# WL_BPF.net
KiCad netlist of a schematic drawn in Altium Designer
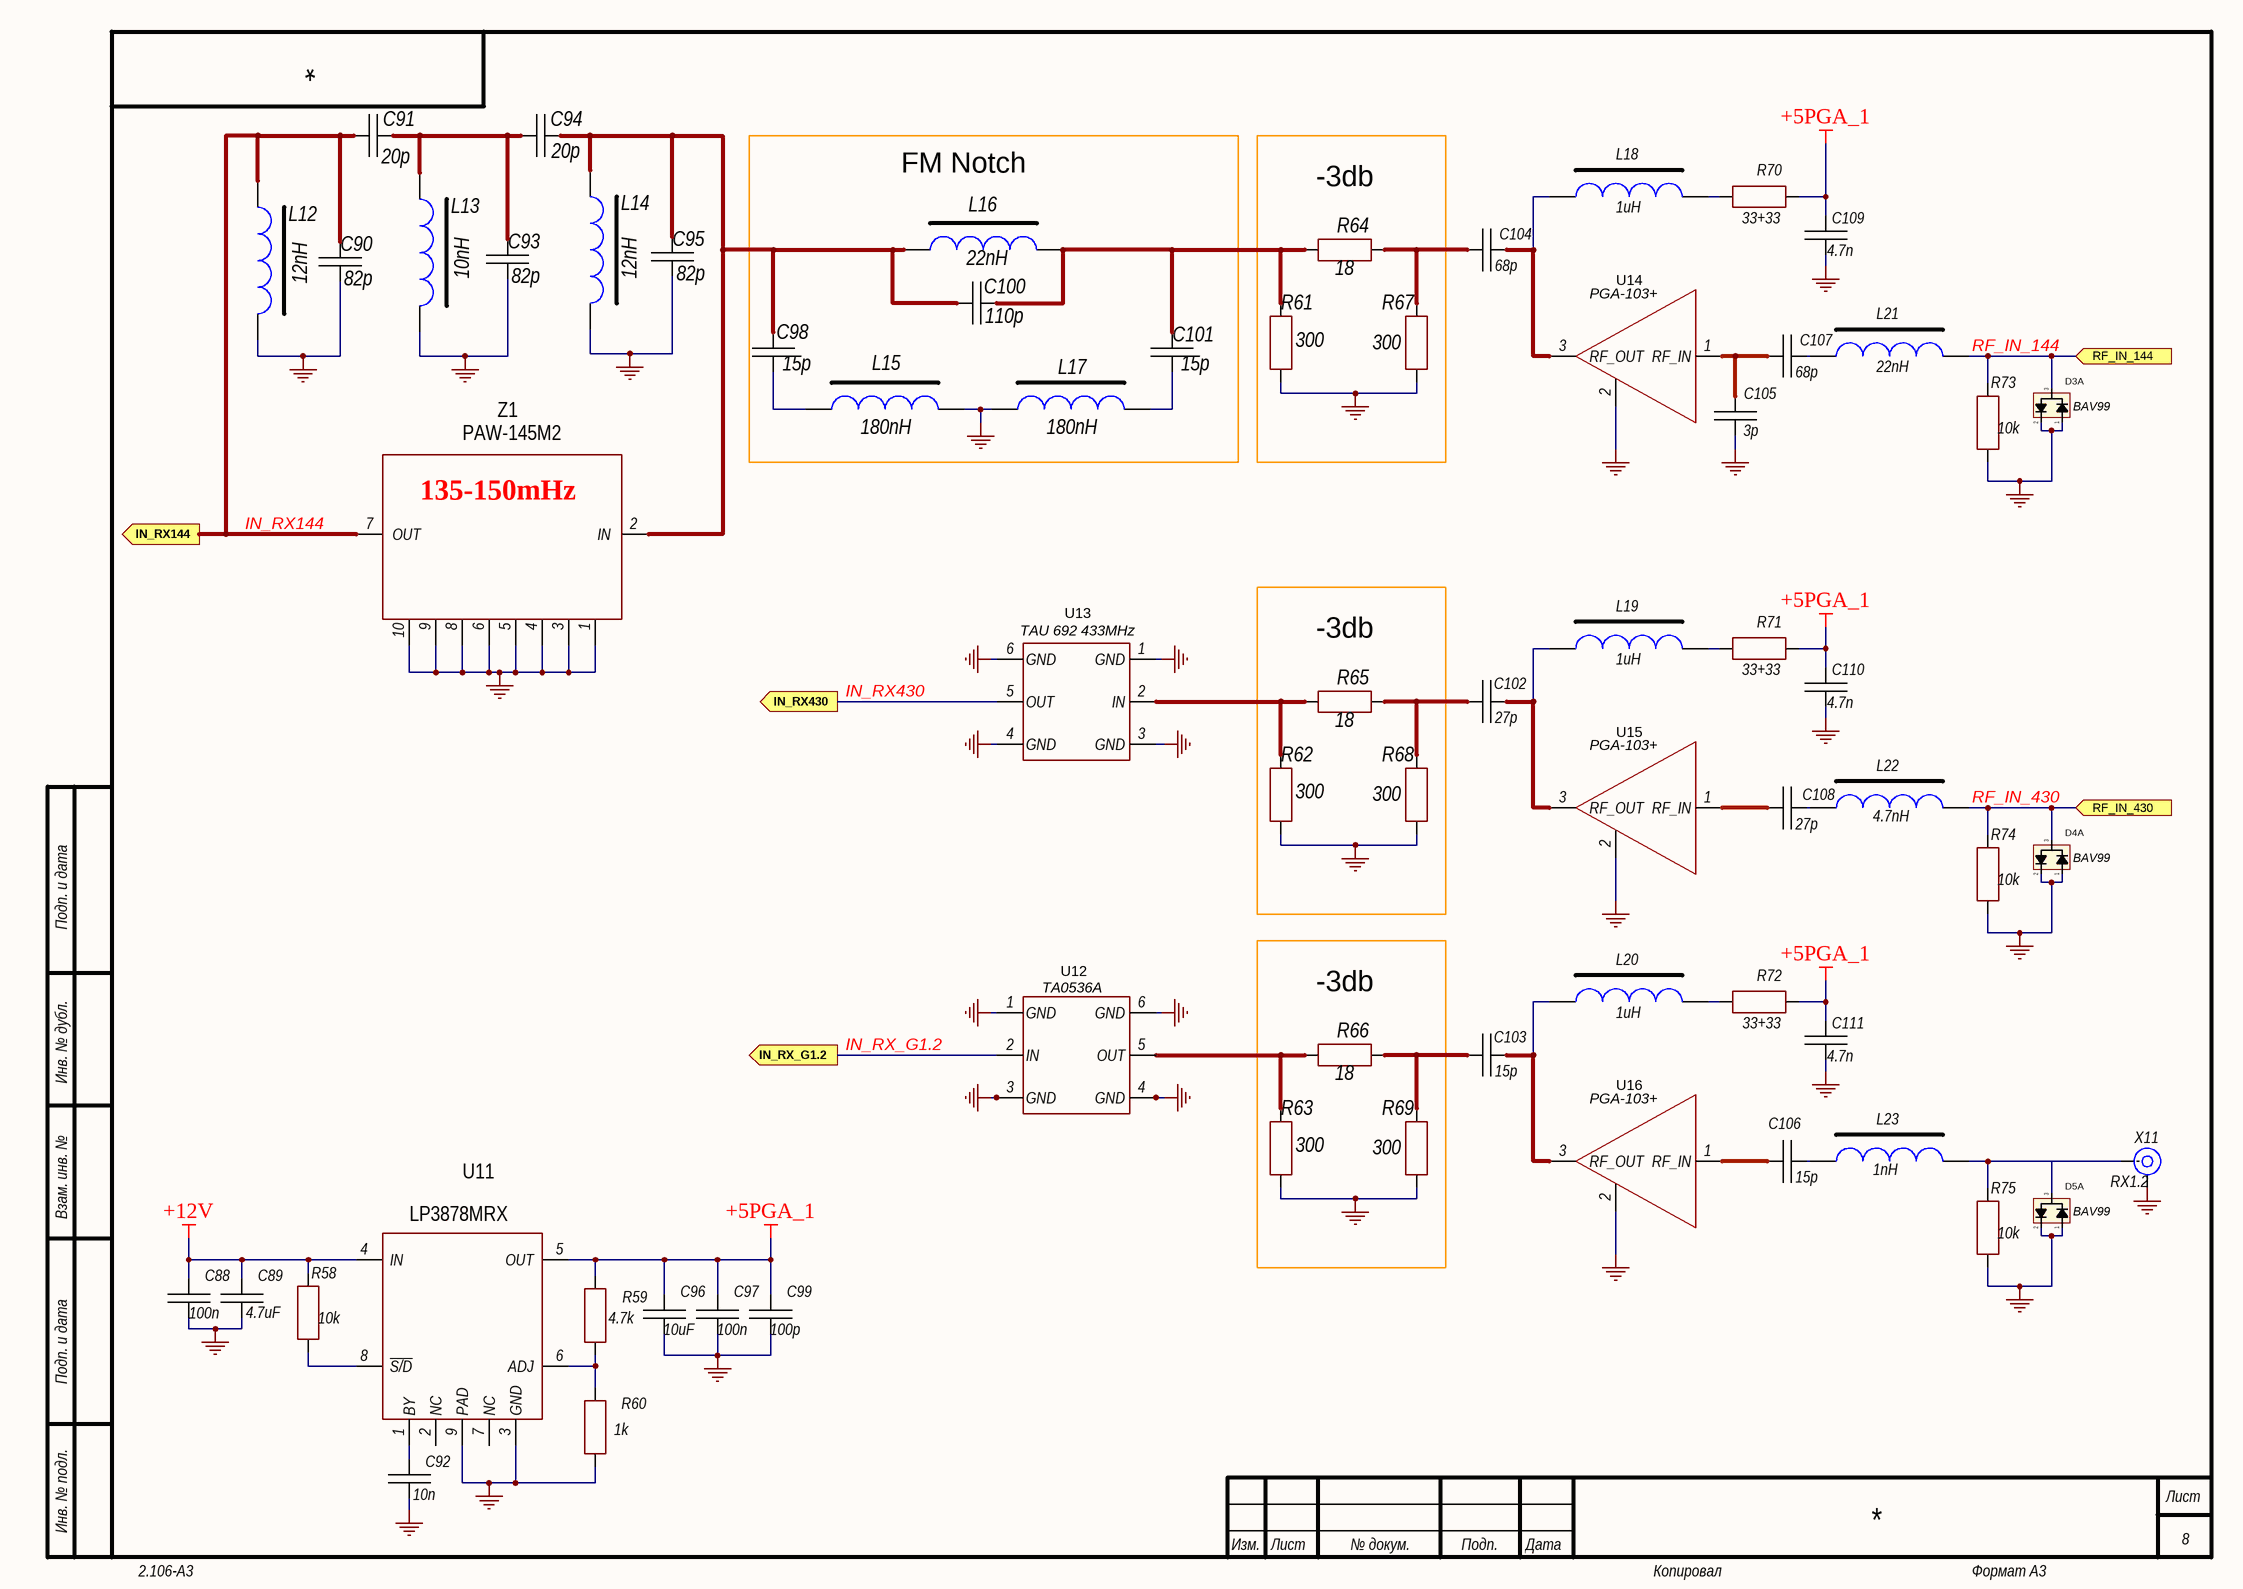
[diagram p0: WL_BPF.SchDoc]

(export (version "E")
  (design (tool "Eeschema 10.0.6"))
  (components
    (comp (ref "C88")
      (value "100n")
      (footprint "standard:CH0805C")
      (libsource (lib "Discrete") (part "Capacitor"))
    )
    (comp (ref "C89")
      (value "4.7uF")
      (footprint "standard:CH0805C")
      (libsource (lib "Discrete") (part "Capacitor"))
    )
    (comp (ref "C90")
      (value "82p")
      (footprint "standard:CH0805C")
      (libsource (lib "Discrete") (part "Capacitor"))
    )
    (comp (ref "C91")
      (value "20p")
      (footprint "standard:CH0805C")
      (libsource (lib "Discrete") (part "Capacitor"))
    )
    (comp (ref "C92")
      (value "10n")
      (footprint "standard:CH0805C")
      (libsource (lib "Discrete") (part "Capacitor"))
    )
    (comp (ref "C93")
      (value "82p")
      (footprint "standard:CH0805C")
      (libsource (lib "Discrete") (part "Capacitor"))
    )
    (comp (ref "C94")
      (value "20p")
      (footprint "standard:CH0805C")
      (libsource (lib "Discrete") (part "Capacitor"))
    )
    (comp (ref "C95")
      (value "82p")
      (footprint "standard:CH0805C")
      (libsource (lib "Discrete") (part "Capacitor"))
    )
    (comp (ref "C96")
      (value "10uF")
      (footprint "standard:CH0805C")
      (libsource (lib "Discrete") (part "Capacitor"))
    )
    (comp (ref "C97")
      (value "100n")
      (footprint "standard:CH0805C")
      (libsource (lib "Discrete") (part "Capacitor"))
    )
    (comp (ref "C98")
      (value "15p")
      (footprint "standard:CH0805C")
      (libsource (lib "Discrete") (part "Capacitor"))
    )
    (comp (ref "C99")
      (value "100p")
      (footprint "standard:CH0805C")
      (libsource (lib "Discrete") (part "Capacitor"))
    )
    (comp (ref "C100")
      (value "110p")
      (footprint "standard:CH0805C")
      (libsource (lib "Discrete") (part "Capacitor"))
    )
    (comp (ref "C101")
      (value "15p")
      (footprint "standard:CH0805C")
      (libsource (lib "Discrete") (part "Capacitor"))
    )
    (comp (ref "C102")
      (value "27p")
      (footprint "standard:CH0805C")
      (libsource (lib "Discrete") (part "Capacitor"))
    )
    (comp (ref "C103")
      (value "15p")
      (footprint "standard:CH0603C")
      (libsource (lib "Discrete") (part "Capacitor"))
    )
    (comp (ref "C104")
      (value "68p")
      (footprint "standard:CH0805C")
      (libsource (lib "Discrete") (part "Capacitor"))
    )
    (comp (ref "C105")
      (value "3p")
      (footprint "standard:CH0805C")
      (libsource (lib "Discrete") (part "Capacitor"))
    )
    (comp (ref "C106")
      (value "15p")
      (footprint "standard:CH0603C")
      (libsource (lib "Discrete") (part "Capacitor"))
    )
    (comp (ref "C107")
      (value "68p")
      (footprint "standard:CH0805C")
      (libsource (lib "Discrete") (part "Capacitor"))
    )
    (comp (ref "C108")
      (value "27p")
      (footprint "standard:CH0805C")
      (libsource (lib "Discrete") (part "Capacitor"))
    )
    (comp (ref "C109")
      (value "4.7n")
      (footprint "standard:CH0805C")
      (libsource (lib "Discrete") (part "Capacitor"))
    )
    (comp (ref "C110")
      (value "4.7n")
      (footprint "standard:CH0805C")
      (libsource (lib "Discrete") (part "Capacitor"))
    )
    (comp (ref "C111")
      (value "4.7n")
      (footprint "standard:CH0805C")
      (libsource (lib "Discrete") (part "Capacitor"))
    )
    (comp (ref "D3") (value "BAV99") (footprint "SOT23_132") (libsource (lib "Analog") (part "BAV99")))
    (comp (ref "D4") (value "BAV99") (footprint "SOT23_132") (libsource (lib "Analog") (part "BAV99")))
    (comp (ref "D5") (value "BAV99") (footprint "SOT23_132") (libsource (lib "Analog") (part "BAV99")))
    (comp (ref "L12") (value "12nH") (footprint "L1210") (libsource (lib "") (part "TRANS_1")))
    (comp (ref "L13") (value "10nH") (footprint "L1210") (libsource (lib "") (part "TRANS_1")))
    (comp (ref "L14") (value "12nH") (footprint "L1210") (libsource (lib "") (part "TRANS_1")))
    (comp (ref "L15") (value "180nH") (footprint "L1210") (libsource (lib "") (part "TRANS_1")))
    (comp (ref "L16") (value "22nH") (footprint "L1210") (libsource (lib "") (part "TRANS_1")))
    (comp (ref "L17") (value "180nH") (footprint "L1210") (libsource (lib "") (part "TRANS_1")))
    (comp (ref "L18") (value "1uH") (footprint "L1210") (libsource (lib "Transformers") (part "TRANS")))
    (comp (ref "L19") (value "1uH") (footprint "L1210") (libsource (lib "Transformers") (part "TRANS")))
    (comp (ref "L20") (value "1uH") (footprint "L1210") (libsource (lib "Transformers") (part "TRANS")))
    (comp (ref "L21") (value "22nH") (footprint "L1210") (libsource (lib "Transformers") (part "TRANS")))
    (comp (ref "L22") (value "4.7nH") (footprint "L1210") (libsource (lib "Transformers") (part "TRANS")))
    (comp (ref "L23") (value "1nH") (footprint "L1210") (libsource (lib "Transformers") (part "TRANS")))
    (comp (ref "R58")
      (value "10k")
      (footprint "standard:CH0805R")
      (libsource (lib "Discrete") (part "Resistor"))
    )
    (comp (ref "R59")
      (value "4.7k")
      (footprint "standard:CH0805R")
      (libsource (lib "Discrete") (part "Resistor"))
    )
    (comp (ref "R60")
      (value "1k")
      (footprint "standard:CH0805R")
      (libsource (lib "Discrete") (part "Resistor"))
    )
    (comp (ref "R61") (value "300") (footprint "standard:CH0805R") (libsource (lib "") (part "Resistor_1")))
    (comp (ref "R62") (value "300") (footprint "standard:CH0805R") (libsource (lib "") (part "Resistor_1")))
    (comp (ref "R63") (value "300") (footprint "standard:CH0603R") (libsource (lib "") (part "Resistor_1")))
    (comp (ref "R64") (value "18") (footprint "standard:CH0805R") (libsource (lib "") (part "Resistor_2")))
    (comp (ref "R65") (value "18") (footprint "standard:CH0805R") (libsource (lib "") (part "Resistor_2")))
    (comp (ref "R66") (value "18") (footprint "standard:CH0603R") (libsource (lib "") (part "Resistor_2")))
    (comp (ref "R67") (value "300") (footprint "standard:CH0805R") (libsource (lib "") (part "Resistor_1")))
    (comp (ref "R68") (value "300") (footprint "standard:CH0805R") (libsource (lib "") (part "Resistor_1")))
    (comp (ref "R69") (value "300") (footprint "standard:CH0603R") (libsource (lib "") (part "Resistor_1")))
    (comp (ref "R70") (value "33+33") (footprint "WL_RFFC:CH1206R") (libsource (lib "") (part "Resistor_3")))
    (comp (ref "R71") (value "33+33") (footprint "WL_RFFC:CH1206R") (libsource (lib "") (part "Resistor_3")))
    (comp (ref "R72") (value "33+33") (footprint "WL_RFFC:CH1206R") (libsource (lib "") (part "Resistor_3")))
    (comp (ref "R73")
      (value "10k")
      (footprint "standard:CH0805R")
      (libsource (lib "Discrete") (part "Resistor"))
    )
    (comp (ref "R74")
      (value "10k")
      (footprint "standard:CH0805R")
      (libsource (lib "Discrete") (part "Resistor"))
    )
    (comp (ref "R75") (value "10k") (footprint "standard:CH0805R") (libsource (lib "") (part "Resistor_4")))
    (comp (ref "U11")
      (value "LP3878MRX")
      (footprint "8-SOIC (PAD)")
      (libsource (lib "Power Supplies") (part "LP3878"))
    )
    (comp (ref "U12") (value "TA0536A") (footprint "MA08803") (libsource (lib "") (part "TAU692_1")))
    (comp (ref "U13")
      (value "TAU 692 433MHz")
      (footprint "TAU692")
      (libsource (lib "Digital") (part "TAU692"))
    )
    (comp (ref "U14")
      (value "PGA-103+")
      (footprint "SOT89_123")
      (libsource (lib "Digital") (part "PGA-103+"))
    )
    (comp (ref "U15")
      (value "PGA-103+")
      (footprint "SOT89_123")
      (libsource (lib "Digital") (part "PGA-103+"))
    )
    (comp (ref "U16")
      (value "PGA-103+")
      (footprint "SOT89_123")
      (libsource (lib "Digital") (part "PGA-103+"))
    )
    (comp (ref "X11")
      (value "RX1.2")
      (footprint "CON: u.Fl")
      (description "RF")
      (libsource (lib "Connectors") (part "SMA"))
    )
    (comp (ref "Z1") (value "PAW-145M2") (footprint "PAV") (libsource (lib "Module") (part "SXBP_PAW")))
  )
  (nets
    (net (code "1") (name "+5PGA_1") (class "Default")
      (node (ref "C109") (pin "2") (pinfunction "2_2") (pintype "passive"))
      (node (ref "C110") (pin "2") (pinfunction "2_2") (pintype "passive"))
      (node (ref "C111") (pin "2") (pinfunction "2_2") (pintype "passive"))
      (node (ref "C96") (pin "2") (pinfunction "2_2") (pintype "passive"))
      (node (ref "C97") (pin "2") (pinfunction "2_2") (pintype "passive"))
      (node (ref "C99") (pin "2") (pinfunction "2_2") (pintype "passive"))
      (node (ref "R59") (pin "2") (pinfunction "2_2") (pintype "passive"))
      (node (ref "R70") (pin "2") (pinfunction "2_2") (pintype "passive"))
      (node (ref "R71") (pin "2") (pinfunction "2_2") (pintype "passive"))
      (node (ref "R72") (pin "2") (pinfunction "2_2") (pintype "passive"))
      (node (ref "U11") (pin "5") (pinfunction "OUT_5") (pintype "power_in"))
    )
    (net (code "2") (name "+12V") (class "Default")
      (node (ref "C88") (pin "2") (pinfunction "2_2") (pintype "passive"))
      (node (ref "C89") (pin "2") (pinfunction "2_2") (pintype "passive"))
      (node (ref "R58") (pin "2") (pinfunction "2_2") (pintype "passive"))
      (node (ref "U11") (pin "4") (pinfunction "IN_4") (pintype "power_in"))
    )
    (net (code "3") (name "/IN_RX144") (class "Default")
      (node (ref "C90") (pin "2") (pinfunction "2_2") (pintype "passive"))
      (node (ref "C91") (pin "2") (pinfunction "2_2") (pintype "passive"))
      (node (ref "L12") (pin "1") (pinfunction "1_1") (pintype "passive"))
      (node (ref "Z1") (pin "7") (pinfunction "OUT_7") (pintype "passive"))
    )
    (net (code "4") (name "/IN_RX430") (class "Default")
      (node (ref "U13") (pin "5") (pinfunction "OUT_5") (pintype "passive"))
    )
    (net (code "5") (name "/IN_RX_G1.2") (class "Default")
      (node (ref "U12") (pin "2") (pinfunction "IN_2") (pintype "passive"))
    )
    (net (code "6") (name "/RF_IN_144") (class "Default")
      (node (ref "D3") (pin "3") (pinfunction "9_3") (pintype "passive"))
      (node (ref "L21") (pin "1") (pinfunction "1_1") (pintype "power_in"))
      (node (ref "R73") (pin "2") (pinfunction "2_2") (pintype "passive"))
    )
    (net (code "7") (name "/RF_IN_430") (class "Default")
      (node (ref "D4") (pin "3") (pinfunction "9_3") (pintype "passive"))
      (node (ref "L22") (pin "1") (pinfunction "1_1") (pintype "power_in"))
      (node (ref "R74") (pin "2") (pinfunction "2_2") (pintype "passive"))
    )
    (net (code "8") (name "GND") (class "Default")
      (node (ref "C105") (pin "1") (pinfunction "1_1") (pintype "passive"))
      (node (ref "C109") (pin "1") (pinfunction "1_1") (pintype "passive"))
      (node (ref "C110") (pin "1") (pinfunction "1_1") (pintype "passive"))
      (node (ref "C111") (pin "1") (pinfunction "1_1") (pintype "passive"))
      (node (ref "C88") (pin "1") (pinfunction "1_1") (pintype "passive"))
      (node (ref "C89") (pin "1") (pinfunction "1_1") (pintype "passive"))
      (node (ref "C90") (pin "1") (pinfunction "1_1") (pintype "passive"))
      (node (ref "C92") (pin "1") (pinfunction "1_1") (pintype "passive"))
      (node (ref "C93") (pin "1") (pinfunction "1_1") (pintype "passive"))
      (node (ref "C95") (pin "1") (pinfunction "1_1") (pintype "passive"))
      (node (ref "C96") (pin "1") (pinfunction "1_1") (pintype "passive"))
      (node (ref "C97") (pin "1") (pinfunction "1_1") (pintype "passive"))
      (node (ref "C99") (pin "1") (pinfunction "1_1") (pintype "passive"))
      (node (ref "D3") (pin "1") (pinfunction "11_1") (pintype "passive"))
      (node (ref "D3") (pin "2") (pinfunction "10_2") (pintype "passive"))
      (node (ref "D4") (pin "1") (pinfunction "11_1") (pintype "passive"))
      (node (ref "D4") (pin "2") (pinfunction "10_2") (pintype "passive"))
      (node (ref "D5") (pin "1") (pinfunction "11_1") (pintype "passive"))
      (node (ref "D5") (pin "2") (pinfunction "10_2") (pintype "passive"))
      (node (ref "L12") (pin "2") (pinfunction "2_2") (pintype "passive"))
      (node (ref "L13") (pin "2") (pinfunction "2_2") (pintype "passive"))
      (node (ref "L14") (pin "2") (pinfunction "2_2") (pintype "passive"))
      (node (ref "L15") (pin "2") (pinfunction "2_2") (pintype "passive"))
      (node (ref "L17") (pin "1") (pinfunction "1_1") (pintype "passive"))
      (node (ref "R60") (pin "1") (pinfunction "1_1") (pintype "passive"))
      (node (ref "R61") (pin "2") (pinfunction "2_2") (pintype "passive"))
      (node (ref "R62") (pin "2") (pinfunction "2_2") (pintype "passive"))
      (node (ref "R63") (pin "2") (pinfunction "2_2") (pintype "passive"))
      (node (ref "R67") (pin "2") (pinfunction "2_2") (pintype "passive"))
      (node (ref "R68") (pin "2") (pinfunction "2_2") (pintype "passive"))
      (node (ref "R69") (pin "2") (pinfunction "2_2") (pintype "passive"))
      (node (ref "R73") (pin "1") (pinfunction "1_1") (pintype "passive"))
      (node (ref "R74") (pin "1") (pinfunction "1_1") (pintype "passive"))
      (node (ref "R75") (pin "1") (pinfunction "1_1") (pintype "passive"))
      (node (ref "U11") (pin "3") (pinfunction "GND_3") (pintype "passive"))
      (node (ref "U11") (pin "9") (pinfunction "PAD_9") (pintype "passive"))
      (node (ref "U12") (pin "1") (pinfunction "GND_1") (pintype "passive"))
      (node (ref "U12") (pin "3") (pinfunction "GND_3") (pintype "passive"))
      (node (ref "U12") (pin "4") (pinfunction "GND_4") (pintype "passive"))
      (node (ref "U12") (pin "6") (pinfunction "GND_6") (pintype "passive"))
      (node (ref "U13") (pin "1") (pinfunction "GND_1") (pintype "passive"))
      (node (ref "U13") (pin "3") (pinfunction "GND_3") (pintype "passive"))
      (node (ref "U13") (pin "4") (pinfunction "GND_4") (pintype "passive"))
      (node (ref "U13") (pin "6") (pinfunction "GND_6") (pintype "passive"))
      (node (ref "U14") (pin "2") (pinfunction "GND_2") (pintype "passive"))
      (node (ref "U15") (pin "2") (pinfunction "GND_2") (pintype "passive"))
      (node (ref "U16") (pin "2") (pinfunction "GND_2") (pintype "passive"))
      (node (ref "X11") (pin "2") (pinfunction "IN_2") (pintype "passive"))
      (node (ref "Z1") (pin "1") (pinfunction "RESET_1") (pintype "passive"))
      (node (ref "Z1") (pin "10") (pinfunction "TXD_10") (pintype "passive"))
      (node (ref "Z1") (pin "3") (pinfunction "CH_PD_3") (pintype "passive"))
      (node (ref "Z1") (pin "4") (pinfunction "GPIO16_4") (pintype "passive"))
      (node (ref "Z1") (pin "5") (pinfunction "GPIO14_5") (pintype "passive"))
      (node (ref "Z1") (pin "6") (pinfunction "GPIO0_6") (pintype "passive"))
      (node (ref "Z1") (pin "8") (pinfunction "GPIO5_8") (pintype "passive"))
      (node (ref "Z1") (pin "9") (pinfunction "RXD_9") (pintype "passive"))
    )
    (net (code "9") (name "Net-(C91-Pad1)") (class "Default")
      (node (ref "C91") (pin "1") (pinfunction "1_1") (pintype "passive"))
      (node (ref "C93") (pin "2") (pinfunction "2_2") (pintype "passive"))
      (node (ref "C94") (pin "2") (pinfunction "2_2") (pintype "passive"))
      (node (ref "L13") (pin "1") (pinfunction "1_1") (pintype "passive"))
    )
    (net (code "10") (name "Net-(C98-Pad1)") (class "Default")
      (node (ref "C98") (pin "1") (pinfunction "1_1") (pintype "passive"))
      (node (ref "L15") (pin "1") (pinfunction "1_1") (pintype "passive"))
    )
    (net (code "11") (name "Net-(C100-Pad2)") (class "Default")
      (node (ref "C100") (pin "2") (pinfunction "2_2") (pintype "passive"))
      (node (ref "C101") (pin "2") (pinfunction "2_2") (pintype "passive"))
      (node (ref "L16") (pin "2") (pinfunction "2_2") (pintype "passive"))
      (node (ref "R61") (pin "1") (pinfunction "1_1") (pintype "passive"))
      (node (ref "R64") (pin "2") (pinfunction "2_2") (pintype "passive"))
    )
    (net (code "12") (name "Net-(C101-Pad1)") (class "Default")
      (node (ref "C101") (pin "1") (pinfunction "1_1") (pintype "passive"))
      (node (ref "L17") (pin "2") (pinfunction "2_2") (pintype "passive"))
    )
    (net (code "13") (name "Net-(C102-Pad1)") (class "Default")
      (node (ref "C102") (pin "1") (pinfunction "1_1") (pintype "passive"))
      (node (ref "R65") (pin "1") (pinfunction "1_1") (pintype "passive"))
      (node (ref "R68") (pin "1") (pinfunction "1_1") (pintype "passive"))
    )
    (net (code "14") (name "Net-(C103-Pad1)") (class "Default")
      (node (ref "C103") (pin "1") (pinfunction "1_1") (pintype "passive"))
      (node (ref "R66") (pin "1") (pinfunction "1_1") (pintype "passive"))
      (node (ref "R69") (pin "1") (pinfunction "1_1") (pintype "passive"))
    )
    (net (code "15") (name "Net-(C104-Pad1)") (class "Default")
      (node (ref "C104") (pin "1") (pinfunction "1_1") (pintype "passive"))
      (node (ref "R64") (pin "1") (pinfunction "1_1") (pintype "passive"))
      (node (ref "R67") (pin "1") (pinfunction "1_1") (pintype "passive"))
    )
    (net (code "16") (name "Net-(C106-Pad2)") (class "Default")
      (node (ref "C106") (pin "2") (pinfunction "2_2") (pintype "passive"))
      (node (ref "L23") (pin "2") (pinfunction "2_2") (pintype "power_in"))
    )
    (net (code "17") (name "Net-(C107-Pad2)") (class "Default")
      (node (ref "C107") (pin "2") (pinfunction "2_2") (pintype "passive"))
      (node (ref "L21") (pin "2") (pinfunction "2_2") (pintype "power_in"))
    )
    (net (code "18") (name "Net-(C108-Pad2)") (class "Default")
      (node (ref "C108") (pin "2") (pinfunction "2_2") (pintype "passive"))
      (node (ref "L22") (pin "2") (pinfunction "2_2") (pintype "power_in"))
    )
    (net (code "19") (name "Net-(D5A-9)") (class "Default")
      (node (ref "D5") (pin "3") (pinfunction "9_3") (pintype "passive"))
      (node (ref "L23") (pin "1") (pinfunction "1_1") (pintype "power_in"))
      (node (ref "R75") (pin "2") (pinfunction "2_2") (pintype "passive"))
      (node (ref "X11") (pin "1") (pinfunction "IN_1") (pintype "passive"))
    )
    (net (code "20") (name "Net-(L18-Pad1)") (class "Default")
      (node (ref "L18") (pin "1") (pinfunction "1_1") (pintype "power_in"))
      (node (ref "R70") (pin "1") (pinfunction "1_1") (pintype "passive"))
    )
    (net (code "21") (name "Net-(L19-Pad1)") (class "Default")
      (node (ref "L19") (pin "1") (pinfunction "1_1") (pintype "power_in"))
      (node (ref "R71") (pin "1") (pinfunction "1_1") (pintype "passive"))
    )
    (net (code "22") (name "Net-(L20-Pad1)") (class "Default")
      (node (ref "L20") (pin "1") (pinfunction "1_1") (pintype "power_in"))
      (node (ref "R72") (pin "1") (pinfunction "1_1") (pintype "passive"))
    )
    (net (code "23") (name "Net-(U11-ADJ)") (class "Default")
      (node (ref "R59") (pin "1") (pinfunction "1_1") (pintype "passive"))
      (node (ref "R60") (pin "2") (pinfunction "2_2") (pintype "passive"))
      (node (ref "U11") (pin "6") (pinfunction "ADJ_6") (pintype "passive"))
    )
    (net (code "24") (name "Net-(U11-BY)") (class "Default")
      (node (ref "C92") (pin "2") (pinfunction "2_2") (pintype "passive"))
      (node (ref "U11") (pin "1") (pinfunction "BY_1") (pintype "passive"))
    )
    (net (code "25") (name "Net-(U11-~{S{slash}D})") (class "Default")
      (node (ref "R58") (pin "1") (pinfunction "1_1") (pintype "passive"))
      (node (ref "U11") (pin "8") (pinfunction "~{S/D}_8") (pintype "power_in"))
    )
    (net (code "26") (name "Net-(U12-OUT)") (class "Default")
      (node (ref "R63") (pin "1") (pinfunction "1_1") (pintype "passive"))
      (node (ref "R66") (pin "2") (pinfunction "2_2") (pintype "passive"))
      (node (ref "U12") (pin "5") (pinfunction "OUT_5") (pintype "passive"))
    )
    (net (code "27") (name "Net-(U13-IN)") (class "Default")
      (node (ref "R62") (pin "1") (pinfunction "1_1") (pintype "passive"))
      (node (ref "R65") (pin "2") (pinfunction "2_2") (pintype "passive"))
      (node (ref "U13") (pin "2") (pinfunction "IN_2") (pintype "passive"))
    )
    (net (code "28") (name "Net-(U14-RF_IN)") (class "Default")
      (node (ref "C105") (pin "2") (pinfunction "2_2") (pintype "passive"))
      (node (ref "C107") (pin "1") (pinfunction "1_1") (pintype "passive"))
      (node (ref "U14") (pin "1") (pinfunction "RF_IN_1") (pintype "passive"))
    )
    (net (code "29") (name "Net-(U14-RF_OUT)") (class "Default")
      (node (ref "C104") (pin "2") (pinfunction "2_2") (pintype "passive"))
      (node (ref "L18") (pin "2") (pinfunction "2_2") (pintype "power_in"))
      (node (ref "U14") (pin "3") (pinfunction "RF_OUT_3") (pintype "passive"))
    )
    (net (code "30") (name "Net-(U15-RF_IN)") (class "Default")
      (node (ref "C108") (pin "1") (pinfunction "1_1") (pintype "passive"))
      (node (ref "U15") (pin "1") (pinfunction "RF_IN_1") (pintype "passive"))
    )
    (net (code "31") (name "Net-(U15-RF_OUT)") (class "Default")
      (node (ref "C102") (pin "2") (pinfunction "2_2") (pintype "passive"))
      (node (ref "L19") (pin "2") (pinfunction "2_2") (pintype "power_in"))
      (node (ref "U15") (pin "3") (pinfunction "RF_OUT_3") (pintype "passive"))
    )
    (net (code "32") (name "Net-(U16-RF_IN)") (class "Default")
      (node (ref "C106") (pin "1") (pinfunction "1_1") (pintype "passive"))
      (node (ref "U16") (pin "1") (pinfunction "RF_IN_1") (pintype "passive"))
    )
    (net (code "33") (name "Net-(U16-RF_OUT)") (class "Default")
      (node (ref "C103") (pin "2") (pinfunction "2_2") (pintype "passive"))
      (node (ref "L20") (pin "2") (pinfunction "2_2") (pintype "power_in"))
      (node (ref "U16") (pin "3") (pinfunction "RF_OUT_3") (pintype "passive"))
    )
    (net (code "34") (name "Net-(Z1-IN)") (class "Default")
      (node (ref "C100") (pin "1") (pinfunction "1_1") (pintype "passive"))
      (node (ref "C94") (pin "1") (pinfunction "1_1") (pintype "passive"))
      (node (ref "C95") (pin "2") (pinfunction "2_2") (pintype "passive"))
      (node (ref "C98") (pin "2") (pinfunction "2_2") (pintype "passive"))
      (node (ref "L14") (pin "1") (pinfunction "1_1") (pintype "passive"))
      (node (ref "L16") (pin "1") (pinfunction "1_1") (pintype "passive"))
      (node (ref "Z1") (pin "2") (pinfunction "IN_2") (pintype "passive"))
    )
    (net (code "35") (name "unconnected-(U11-NC-Pad2)") (class "Default")
      (node (ref "U11") (pin "2") (pinfunction "NC_2") (pintype "passive"))
    )
    (net (code "36") (name "unconnected-(U11-NC-Pad7)") (class "Default")
      (node (ref "U11") (pin "7") (pinfunction "NC_7") (pintype "passive"))
    )
  )
)
